# design.net
KiCad netlist of a schematic drawn in Altium Designer
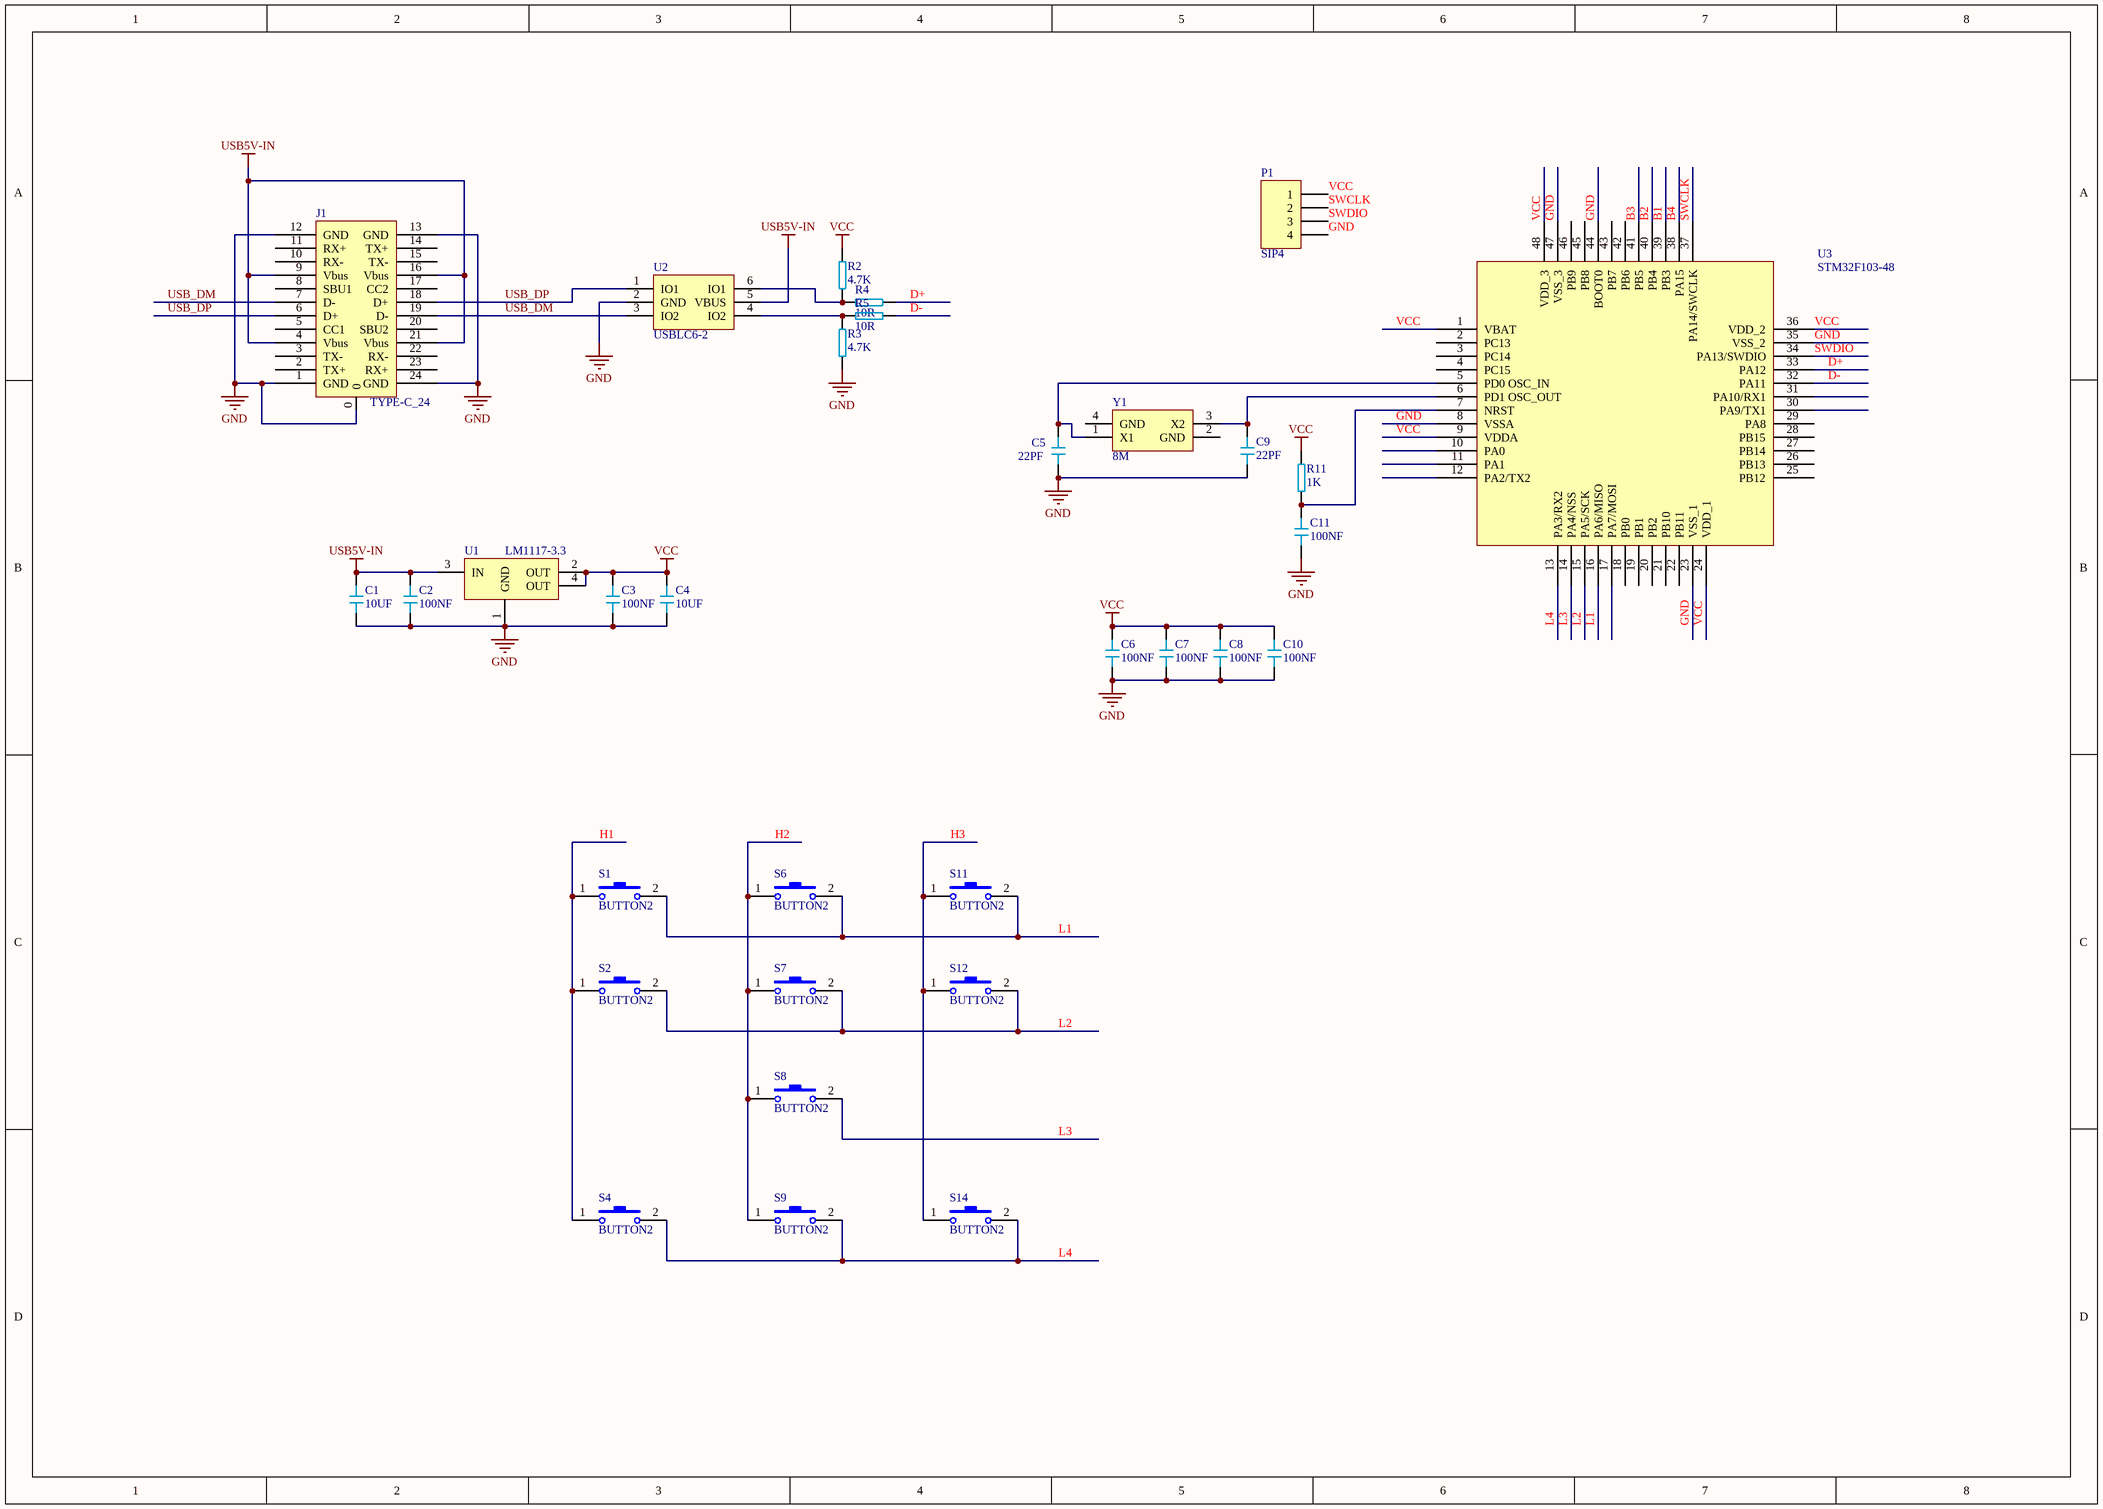
[diagram p0: 原理图.SchDoc]

(export (version "E")
  (design (tool "Eeschema 10.0.6"))
  (components
    (comp (ref "C1")
      (value "10UF")
      (footprint "C0603")
      (description "贴片电容")
      (libsource (lib "base") (part "C0603"))
    )
    (comp (ref "C2")
      (value "100NF")
      (footprint "C0603")
      (description "贴片电容")
      (libsource (lib "base") (part "C0603"))
    )
    (comp (ref "C3")
      (value "100NF")
      (footprint "C0603")
      (description "贴片电容")
      (libsource (lib "base") (part "C0603"))
    )
    (comp (ref "C4")
      (value "10UF")
      (footprint "C0603")
      (description "贴片电容")
      (libsource (lib "base") (part "C0603"))
    )
    (comp (ref "C5")
      (value "22PF")
      (footprint "C0603")
      (description "贴片电容")
      (libsource (lib "base") (part "C0603"))
    )
    (comp (ref "C6")
      (value "100NF")
      (footprint "C0603")
      (description "贴片电容")
      (libsource (lib "base") (part "C0603"))
    )
    (comp (ref "C7")
      (value "100NF")
      (footprint "C0603")
      (description "贴片电容")
      (libsource (lib "base") (part "C0603"))
    )
    (comp (ref "C8")
      (value "100NF")
      (footprint "C0603")
      (description "贴片电容")
      (libsource (lib "base") (part "C0603"))
    )
    (comp (ref "C9")
      (value "22PF")
      (footprint "C0603")
      (description "贴片电容")
      (libsource (lib "base") (part "C0603"))
    )
    (comp (ref "C10")
      (value "100NF")
      (footprint "C0603")
      (description "贴片电容")
      (libsource (lib "base") (part "C0603"))
    )
    (comp (ref "C11")
      (value "100NF")
      (footprint "C0603")
      (description "贴片电容")
      (libsource (lib "base") (part "C0603"))
    )
    (comp (ref "J1")
      (value "TYPE-C_24")
      (footprint "TYPE-C24P")
      (libsource (lib "Schlib_pok") (part "TYPE-C_24"))
    )
    (comp (ref "P1")
      (value "SIP4")
      (footprint "SIP4")
      (description "连接器")
      (fields (field (name "PUBLISHER") "Altium Limited"))
      (libsource (lib "base") (part "SIP4"))
    )
    (comp (ref "R2")
      (value "4.7K")
      (footprint "R0603")
      (description "贴片电阻")
      (libsource (lib "base") (part "R-0603"))
    )
    (comp (ref "R3")
      (value "4.7K")
      (footprint "R0603")
      (description "贴片电阻")
      (libsource (lib "base") (part "R-0603"))
    )
    (comp (ref "R4")
      (value "10R")
      (footprint "R0603")
      (description "贴片电阻")
      (libsource (lib "base") (part "R-0603"))
    )
    (comp (ref "R5")
      (value "10R")
      (footprint "R0603")
      (description "贴片电阻")
      (libsource (lib "base") (part "R-0603"))
    )
    (comp (ref "R11")
      (value "1K")
      (footprint "R0603")
      (description "贴片电阻")
      (libsource (lib "base") (part "R-0603"))
    )
    (comp (ref "S1")
      (value "BUTTON2")
      (footprint "KEY")
      (description "按钮")
      (fields (field (name "PUBLISHER") "Altium Limited"))
      (libsource (lib "base") (part "BUTTON2"))
    )
    (comp (ref "S2")
      (value "BUTTON2")
      (footprint "KEY")
      (description "按钮")
      (fields (field (name "PUBLISHER") "Altium Limited"))
      (libsource (lib "base") (part "BUTTON2"))
    )
    (comp (ref "S4")
      (value "BUTTON2")
      (footprint "KEY")
      (description "按钮")
      (fields (field (name "PUBLISHER") "Altium Limited"))
      (libsource (lib "base") (part "BUTTON2"))
    )
    (comp (ref "S6")
      (value "BUTTON2")
      (footprint "KEY")
      (description "按钮")
      (fields (field (name "PUBLISHER") "Altium Limited"))
      (libsource (lib "base") (part "BUTTON2"))
    )
    (comp (ref "S7")
      (value "BUTTON2")
      (footprint "KEY")
      (description "按钮")
      (fields (field (name "PUBLISHER") "Altium Limited"))
      (libsource (lib "base") (part "BUTTON2"))
    )
    (comp (ref "S8")
      (value "BUTTON2")
      (footprint "KEY")
      (description "按钮")
      (fields (field (name "PUBLISHER") "Altium Limited"))
      (libsource (lib "base") (part "BUTTON2"))
    )
    (comp (ref "S9")
      (value "BUTTON2")
      (footprint "KEY")
      (description "按钮")
      (fields (field (name "PUBLISHER") "Altium Limited"))
      (libsource (lib "base") (part "BUTTON2"))
    )
    (comp (ref "S11")
      (value "BUTTON2")
      (footprint "KEY")
      (description "按钮")
      (fields (field (name "PUBLISHER") "Altium Limited"))
      (libsource (lib "base") (part "BUTTON2"))
    )
    (comp (ref "S12")
      (value "BUTTON2")
      (footprint "KEY")
      (description "按钮")
      (fields (field (name "PUBLISHER") "Altium Limited"))
      (libsource (lib "base") (part "BUTTON2"))
    )
    (comp (ref "S14")
      (value "BUTTON2")
      (footprint "KEY")
      (description "按钮")
      (fields (field (name "PUBLISHER") "Altium Limited"))
      (libsource (lib "base") (part "BUTTON2"))
    )
    (comp (ref "U1")
      (value "LM1117-3.3")
      (footprint "SOT223")
      (description "芯片")
      (fields (field (name "PUBLISHER") "Altium Limited"))
      (libsource (lib "base") (part "1117"))
    )
    (comp (ref "U2") (value "USBLC6-2") (footprint "SOT23-6") (libsource (lib "Chip") (part "USBLC6-2")))
    (comp (ref "U3")
      (value "STM32F103-48")
      (footprint "LQFP48")
      (libsource (lib "Chip") (part "STM32F103-48"))
    )
    (comp (ref "Y1")
      (value "8M")
      (footprint "XTAL-3225-4")
      (description "无源晶振")
      (fields (field (name "PUBLISHER") "Altium Limited"))
      (libsource (lib "base") (part "XTAL-4-W"))
    )
  )
  (nets
    (net (code "1") (name "/B1") (class "Default")
      (node (ref "U3") (pin "39") (pinfunction "PB3_39") (pintype "passive"))
    )
    (net (code "2") (name "/B2") (class "Default")
      (node (ref "U3") (pin "40") (pinfunction "PB4_40") (pintype "passive"))
    )
    (net (code "3") (name "/B3") (class "Default")
      (node (ref "U3") (pin "41") (pinfunction "PB5_41") (pintype "passive"))
    )
    (net (code "4") (name "/B4") (class "Default")
      (node (ref "U3") (pin "38") (pinfunction "PA15_38") (pintype "passive"))
    )
    (net (code "5") (name "/D+") (class "Default")
      (node (ref "R4") (pin "2") (pinfunction "2_2") (pintype "passive"))
      (node (ref "U3") (pin "33") (pinfunction "PA12_33") (pintype "passive"))
    )
    (net (code "6") (name "/D-") (class "Default")
      (node (ref "R5") (pin "2") (pinfunction "2_2") (pintype "passive"))
      (node (ref "U3") (pin "32") (pinfunction "PA11_32") (pintype "passive"))
    )
    (net (code "7") (name "/H1") (class "Default")
      (node (ref "S1") (pin "1") (pinfunction "1_1") (pintype "passive"))
      (node (ref "S2") (pin "1") (pinfunction "1_1") (pintype "passive"))
      (node (ref "S4") (pin "1") (pinfunction "1_1") (pintype "passive"))
    )
    (net (code "8") (name "/H2") (class "Default")
      (node (ref "S6") (pin "1") (pinfunction "1_1") (pintype "passive"))
      (node (ref "S7") (pin "1") (pinfunction "1_1") (pintype "passive"))
      (node (ref "S8") (pin "1") (pinfunction "1_1") (pintype "passive"))
      (node (ref "S9") (pin "1") (pinfunction "1_1") (pintype "passive"))
    )
    (net (code "9") (name "/H3") (class "Default")
      (node (ref "S11") (pin "1") (pinfunction "1_1") (pintype "passive"))
      (node (ref "S12") (pin "1") (pinfunction "1_1") (pintype "passive"))
      (node (ref "S14") (pin "1") (pinfunction "1_1") (pintype "passive"))
    )
    (net (code "10") (name "/L1") (class "Default")
      (node (ref "S1") (pin "2") (pinfunction "2_2") (pintype "passive"))
      (node (ref "S11") (pin "2") (pinfunction "2_2") (pintype "passive"))
      (node (ref "S6") (pin "2") (pinfunction "2_2") (pintype "passive"))
      (node (ref "U3") (pin "16") (pinfunction "PA6/MISO_16") (pintype "passive"))
    )
    (net (code "11") (name "/L2") (class "Default")
      (node (ref "S12") (pin "2") (pinfunction "2_2") (pintype "passive"))
      (node (ref "S2") (pin "2") (pinfunction "2_2") (pintype "passive"))
      (node (ref "S7") (pin "2") (pinfunction "2_2") (pintype "passive"))
      (node (ref "U3") (pin "15") (pinfunction "PA5/SCK_15") (pintype "passive"))
    )
    (net (code "12") (name "/L3") (class "Default")
      (node (ref "S8") (pin "2") (pinfunction "2_2") (pintype "passive"))
      (node (ref "U3") (pin "14") (pinfunction "PA4/NSS_14") (pintype "passive"))
    )
    (net (code "13") (name "/L4") (class "Default")
      (node (ref "S14") (pin "2") (pinfunction "2_2") (pintype "passive"))
      (node (ref "S4") (pin "2") (pinfunction "2_2") (pintype "passive"))
      (node (ref "S9") (pin "2") (pinfunction "2_2") (pintype "passive"))
      (node (ref "U3") (pin "13") (pinfunction "PA3/RX2_13") (pintype "passive"))
    )
    (net (code "14") (name "/SWCLK") (class "Default")
      (node (ref "P1") (pin "2") (pinfunction "2_2") (pintype "passive"))
      (node (ref "U3") (pin "37") (pinfunction "PA14/SWCLK_37") (pintype "passive"))
    )
    (net (code "15") (name "/SWDIO") (class "Default")
      (node (ref "P1") (pin "3") (pinfunction "3_3") (pintype "passive"))
      (node (ref "U3") (pin "34") (pinfunction "PA13/SWDIO_34") (pintype "passive"))
    )
    (net (code "16") (name "/USB_DM") (class "Default")
      (node (ref "J1") (pin "19") (pinfunction "D-_19") (pintype "passive"))
      (node (ref "J1") (pin "7") (pinfunction "D-_7") (pintype "passive"))
      (node (ref "U2") (pin "3") (pinfunction "IO2_3") (pintype "passive"))
    )
    (net (code "17") (name "/USB_DP") (class "Default")
      (node (ref "J1") (pin "18") (pinfunction "D+_18") (pintype "passive"))
      (node (ref "J1") (pin "6") (pinfunction "D+_6") (pintype "passive"))
      (node (ref "U2") (pin "1") (pinfunction "IO1_1") (pintype "passive"))
    )
    (net (code "18") (name "GND") (class "Default")
      (node (ref "C1") (pin "1") (pinfunction "1_1") (pintype "passive"))
      (node (ref "C10") (pin "1") (pinfunction "1_1") (pintype "passive"))
      (node (ref "C11") (pin "1") (pinfunction "1_1") (pintype "passive"))
      (node (ref "C2") (pin "1") (pinfunction "1_1") (pintype "passive"))
      (node (ref "C3") (pin "1") (pinfunction "1_1") (pintype "passive"))
      (node (ref "C4") (pin "1") (pinfunction "1_1") (pintype "passive"))
      (node (ref "C5") (pin "1") (pinfunction "1_1") (pintype "passive"))
      (node (ref "C6") (pin "1") (pinfunction "1_1") (pintype "passive"))
      (node (ref "C7") (pin "1") (pinfunction "1_1") (pintype "passive"))
      (node (ref "C8") (pin "1") (pinfunction "1_1") (pintype "passive"))
      (node (ref "C9") (pin "1") (pinfunction "1_1") (pintype "passive"))
      (node (ref "J1") (pin "0") (pinfunction "0_0") (pintype "passive"))
      (node (ref "J1") (pin "1") (pinfunction "GND_1") (pintype "passive"))
      (node (ref "J1") (pin "12") (pinfunction "GND_12") (pintype "passive"))
      (node (ref "J1") (pin "13") (pinfunction "GND_13") (pintype "passive"))
      (node (ref "J1") (pin "24") (pinfunction "GND_24") (pintype "passive"))
      (node (ref "P1") (pin "4") (pinfunction "4_4") (pintype "passive"))
      (node (ref "R3") (pin "1") (pinfunction "1_1") (pintype "passive"))
      (node (ref "U1") (pin "1") (pinfunction "GND_1") (pintype "passive"))
      (node (ref "U2") (pin "2") (pinfunction "GND_2") (pintype "passive"))
      (node (ref "U3") (pin "23") (pinfunction "VSS_1_23") (pintype "passive"))
      (node (ref "U3") (pin "35") (pinfunction "VSS_2_35") (pintype "passive"))
      (node (ref "U3") (pin "44") (pinfunction "BOOT0_44") (pintype "passive"))
      (node (ref "U3") (pin "47") (pinfunction "VSS_3_47") (pintype "passive"))
      (node (ref "U3") (pin "8") (pinfunction "VSSA_8") (pintype "passive"))
    )
    (net (code "19") (name "Net-(R2-Pad1)") (class "Default")
      (node (ref "R2") (pin "1") (pinfunction "1_1") (pintype "passive"))
      (node (ref "R4") (pin "1") (pinfunction "1_1") (pintype "passive"))
      (node (ref "U2") (pin "6") (pinfunction "IO1_6") (pintype "passive"))
    )
    (net (code "20") (name "Net-(R3-Pad2)") (class "Default")
      (node (ref "R3") (pin "2") (pinfunction "2_2") (pintype "passive"))
      (node (ref "R5") (pin "1") (pinfunction "1_1") (pintype "passive"))
      (node (ref "U2") (pin "4") (pinfunction "IO2_4") (pintype "passive"))
    )
    (net (code "21") (name "Net-(U3-NRST)") (class "Default")
      (node (ref "C11") (pin "2") (pinfunction "2_2") (pintype "passive"))
      (node (ref "R11") (pin "1") (pinfunction "1_1") (pintype "passive"))
      (node (ref "U3") (pin "7") (pinfunction "NRST_7") (pintype "passive"))
    )
    (net (code "22") (name "Net-(U3-PD0_OSC_IN)") (class "Default")
      (node (ref "C5") (pin "2") (pinfunction "2_2") (pintype "passive"))
      (node (ref "U3") (pin "5") (pinfunction "PD0_OSC_IN_5") (pintype "passive"))
      (node (ref "Y1") (pin "1") (pinfunction "X1_1") (pintype "passive"))
    )
    (net (code "23") (name "Net-(U3-PD1_OSC_OUT)") (class "Default")
      (node (ref "C9") (pin "2") (pinfunction "2_2") (pintype "passive"))
      (node (ref "U3") (pin "6") (pinfunction "PD1_OSC_OUT_6") (pintype "passive"))
      (node (ref "Y1") (pin "3") (pinfunction "X2_3") (pintype "passive"))
    )
    (net (code "24") (name "USB5V-IN") (class "Default")
      (node (ref "C1") (pin "2") (pinfunction "2_2") (pintype "passive"))
      (node (ref "C2") (pin "2") (pinfunction "2_2") (pintype "passive"))
      (node (ref "J1") (pin "16") (pinfunction "Vbus_16") (pintype "passive"))
      (node (ref "J1") (pin "21") (pinfunction "Vbus_21") (pintype "passive"))
      (node (ref "J1") (pin "4") (pinfunction "Vbus_4") (pintype "passive"))
      (node (ref "J1") (pin "9") (pinfunction "Vbus_9") (pintype "passive"))
      (node (ref "U1") (pin "3") (pinfunction "IN_3") (pintype "passive"))
      (node (ref "U2") (pin "5") (pinfunction "VBUS_5") (pintype "passive"))
    )
    (net (code "25") (name "VCC") (class "Default")
      (node (ref "C10") (pin "2") (pinfunction "2_2") (pintype "passive"))
      (node (ref "C3") (pin "2") (pinfunction "2_2") (pintype "passive"))
      (node (ref "C4") (pin "2") (pinfunction "2_2") (pintype "passive"))
      (node (ref "C6") (pin "2") (pinfunction "2_2") (pintype "passive"))
      (node (ref "C7") (pin "2") (pinfunction "2_2") (pintype "passive"))
      (node (ref "C8") (pin "2") (pinfunction "2_2") (pintype "passive"))
      (node (ref "P1") (pin "1") (pinfunction "1_1") (pintype "passive"))
      (node (ref "R11") (pin "2") (pinfunction "2_2") (pintype "passive"))
      (node (ref "R2") (pin "2") (pinfunction "2_2") (pintype "passive"))
      (node (ref "U1") (pin "2") (pinfunction "OUT_2") (pintype "passive"))
      (node (ref "U1") (pin "4") (pinfunction "OUT_4") (pintype "passive"))
      (node (ref "U3") (pin "1") (pinfunction "VBAT_1") (pintype "passive"))
      (node (ref "U3") (pin "24") (pinfunction "VDD_1_24") (pintype "passive"))
      (node (ref "U3") (pin "36") (pinfunction "VDD_2_36") (pintype "passive"))
      (node (ref "U3") (pin "48") (pinfunction "VDD_3_48") (pintype "passive"))
      (node (ref "U3") (pin "9") (pinfunction "VDDA_9") (pintype "passive"))
    )
    (net (code "26") (name "unconnected-(J1-CC1-Pad5)") (class "Default")
      (node (ref "J1") (pin "5") (pinfunction "CC1_5") (pintype "passive"))
    )
    (net (code "27") (name "unconnected-(J1-CC2-Pad17)") (class "Default")
      (node (ref "J1") (pin "17") (pinfunction "CC2_17") (pintype "passive"))
    )
    (net (code "28") (name "unconnected-(J1-RX+-Pad11)") (class "Default")
      (node (ref "J1") (pin "11") (pinfunction "RX+_11") (pintype "passive"))
    )
    (net (code "29") (name "unconnected-(J1-RX+-Pad23)") (class "Default")
      (node (ref "J1") (pin "23") (pinfunction "RX+_23") (pintype "passive"))
    )
    (net (code "30") (name "unconnected-(J1-RX--Pad10)") (class "Default")
      (node (ref "J1") (pin "10") (pinfunction "RX-_10") (pintype "passive"))
    )
    (net (code "31") (name "unconnected-(J1-RX--Pad22)") (class "Default")
      (node (ref "J1") (pin "22") (pinfunction "RX-_22") (pintype "passive"))
    )
    (net (code "32") (name "unconnected-(J1-SBU1-Pad8)") (class "Default")
      (node (ref "J1") (pin "8") (pinfunction "SBU1_8") (pintype "passive"))
    )
    (net (code "33") (name "unconnected-(J1-SBU2-Pad20)") (class "Default")
      (node (ref "J1") (pin "20") (pinfunction "SBU2_20") (pintype "passive"))
    )
    (net (code "34") (name "unconnected-(J1-TX+-Pad2)") (class "Default")
      (node (ref "J1") (pin "2") (pinfunction "TX+_2") (pintype "passive"))
    )
    (net (code "35") (name "unconnected-(J1-TX+-Pad14)") (class "Default")
      (node (ref "J1") (pin "14") (pinfunction "TX+_14") (pintype "passive"))
    )
    (net (code "36") (name "unconnected-(J1-TX--Pad3)") (class "Default")
      (node (ref "J1") (pin "3") (pinfunction "TX-_3") (pintype "passive"))
    )
    (net (code "37") (name "unconnected-(J1-TX--Pad15)") (class "Default")
      (node (ref "J1") (pin "15") (pinfunction "TX-_15") (pintype "passive"))
    )
    (net (code "38") (name "unconnected-(U3-PA0-Pad10)") (class "Default")
      (node (ref "U3") (pin "10") (pinfunction "PA0_10") (pintype "passive"))
    )
    (net (code "39") (name "unconnected-(U3-PA1-Pad11)") (class "Default")
      (node (ref "U3") (pin "11") (pinfunction "PA1_11") (pintype "passive"))
    )
    (net (code "40") (name "unconnected-(U3-PA2{slash}TX2-Pad12)") (class "Default")
      (node (ref "U3") (pin "12") (pinfunction "PA2/TX2_12") (pintype "passive"))
    )
    (net (code "41") (name "unconnected-(U3-PA7{slash}MOSI-Pad17)") (class "Default")
      (node (ref "U3") (pin "17") (pinfunction "PA7/MOSI_17") (pintype "passive"))
    )
    (net (code "42") (name "unconnected-(U3-PA8-Pad29)") (class "Default")
      (node (ref "U3") (pin "29") (pinfunction "PA8_29") (pintype "passive"))
    )
    (net (code "43") (name "unconnected-(U3-PA9{slash}TX1-Pad30)") (class "Default")
      (node (ref "U3") (pin "30") (pinfunction "PA9/TX1_30") (pintype "passive"))
    )
    (net (code "44") (name "unconnected-(U3-PA10{slash}RX1-Pad31)") (class "Default")
      (node (ref "U3") (pin "31") (pinfunction "PA10/RX1_31") (pintype "passive"))
    )
    (net (code "45") (name "unconnected-(U3-PB0-Pad18)") (class "Default")
      (node (ref "U3") (pin "18") (pinfunction "PB0_18") (pintype "passive"))
    )
    (net (code "46") (name "unconnected-(U3-PB1-Pad19)") (class "Default")
      (node (ref "U3") (pin "19") (pinfunction "PB1_19") (pintype "passive"))
    )
    (net (code "47") (name "unconnected-(U3-PB2-Pad20)") (class "Default")
      (node (ref "U3") (pin "20") (pinfunction "PB2_20") (pintype "passive"))
    )
    (net (code "48") (name "unconnected-(U3-PB6-Pad42)") (class "Default")
      (node (ref "U3") (pin "42") (pinfunction "PB6_42") (pintype "passive"))
    )
    (net (code "49") (name "unconnected-(U3-PB7-Pad43)") (class "Default")
      (node (ref "U3") (pin "43") (pinfunction "PB7_43") (pintype "passive"))
    )
    (net (code "50") (name "unconnected-(U3-PB8-Pad45)") (class "Default")
      (node (ref "U3") (pin "45") (pinfunction "PB8_45") (pintype "passive"))
    )
    (net (code "51") (name "unconnected-(U3-PB9-Pad46)") (class "Default")
      (node (ref "U3") (pin "46") (pinfunction "PB9_46") (pintype "passive"))
    )
    (net (code "52") (name "unconnected-(U3-PB10-Pad21)") (class "Default")
      (node (ref "U3") (pin "21") (pinfunction "PB10_21") (pintype "passive"))
    )
    (net (code "53") (name "unconnected-(U3-PB11-Pad22)") (class "Default")
      (node (ref "U3") (pin "22") (pinfunction "PB11_22") (pintype "passive"))
    )
    (net (code "54") (name "unconnected-(U3-PB12-Pad25)") (class "Default")
      (node (ref "U3") (pin "25") (pinfunction "PB12_25") (pintype "passive"))
    )
    (net (code "55") (name "unconnected-(U3-PB13-Pad26)") (class "Default")
      (node (ref "U3") (pin "26") (pinfunction "PB13_26") (pintype "passive"))
    )
    (net (code "56") (name "unconnected-(U3-PB14-Pad27)") (class "Default")
      (node (ref "U3") (pin "27") (pinfunction "PB14_27") (pintype "passive"))
    )
    (net (code "57") (name "unconnected-(U3-PB15-Pad28)") (class "Default")
      (node (ref "U3") (pin "28") (pinfunction "PB15_28") (pintype "passive"))
    )
    (net (code "58") (name "unconnected-(U3-PC13-Pad2)") (class "Default")
      (node (ref "U3") (pin "2") (pinfunction "PC13_2") (pintype "passive"))
    )
    (net (code "59") (name "unconnected-(U3-PC14-Pad3)") (class "Default")
      (node (ref "U3") (pin "3") (pinfunction "PC14_3") (pintype "passive"))
    )
    (net (code "60") (name "unconnected-(U3-PC15-Pad4)") (class "Default")
      (node (ref "U3") (pin "4") (pinfunction "PC15_4") (pintype "passive"))
    )
    (net (code "61") (name "unconnected-(Y1-GND-Pad2)") (class "Default")
      (node (ref "Y1") (pin "2") (pinfunction "GND_2") (pintype "passive"))
    )
    (net (code "62") (name "unconnected-(Y1-GND-Pad4)") (class "Default")
      (node (ref "Y1") (pin "4") (pinfunction "GND_4") (pintype "passive"))
    )
  )
)
